# M1502C.net
KiCad netlist of a schematic drawn in EAGLE
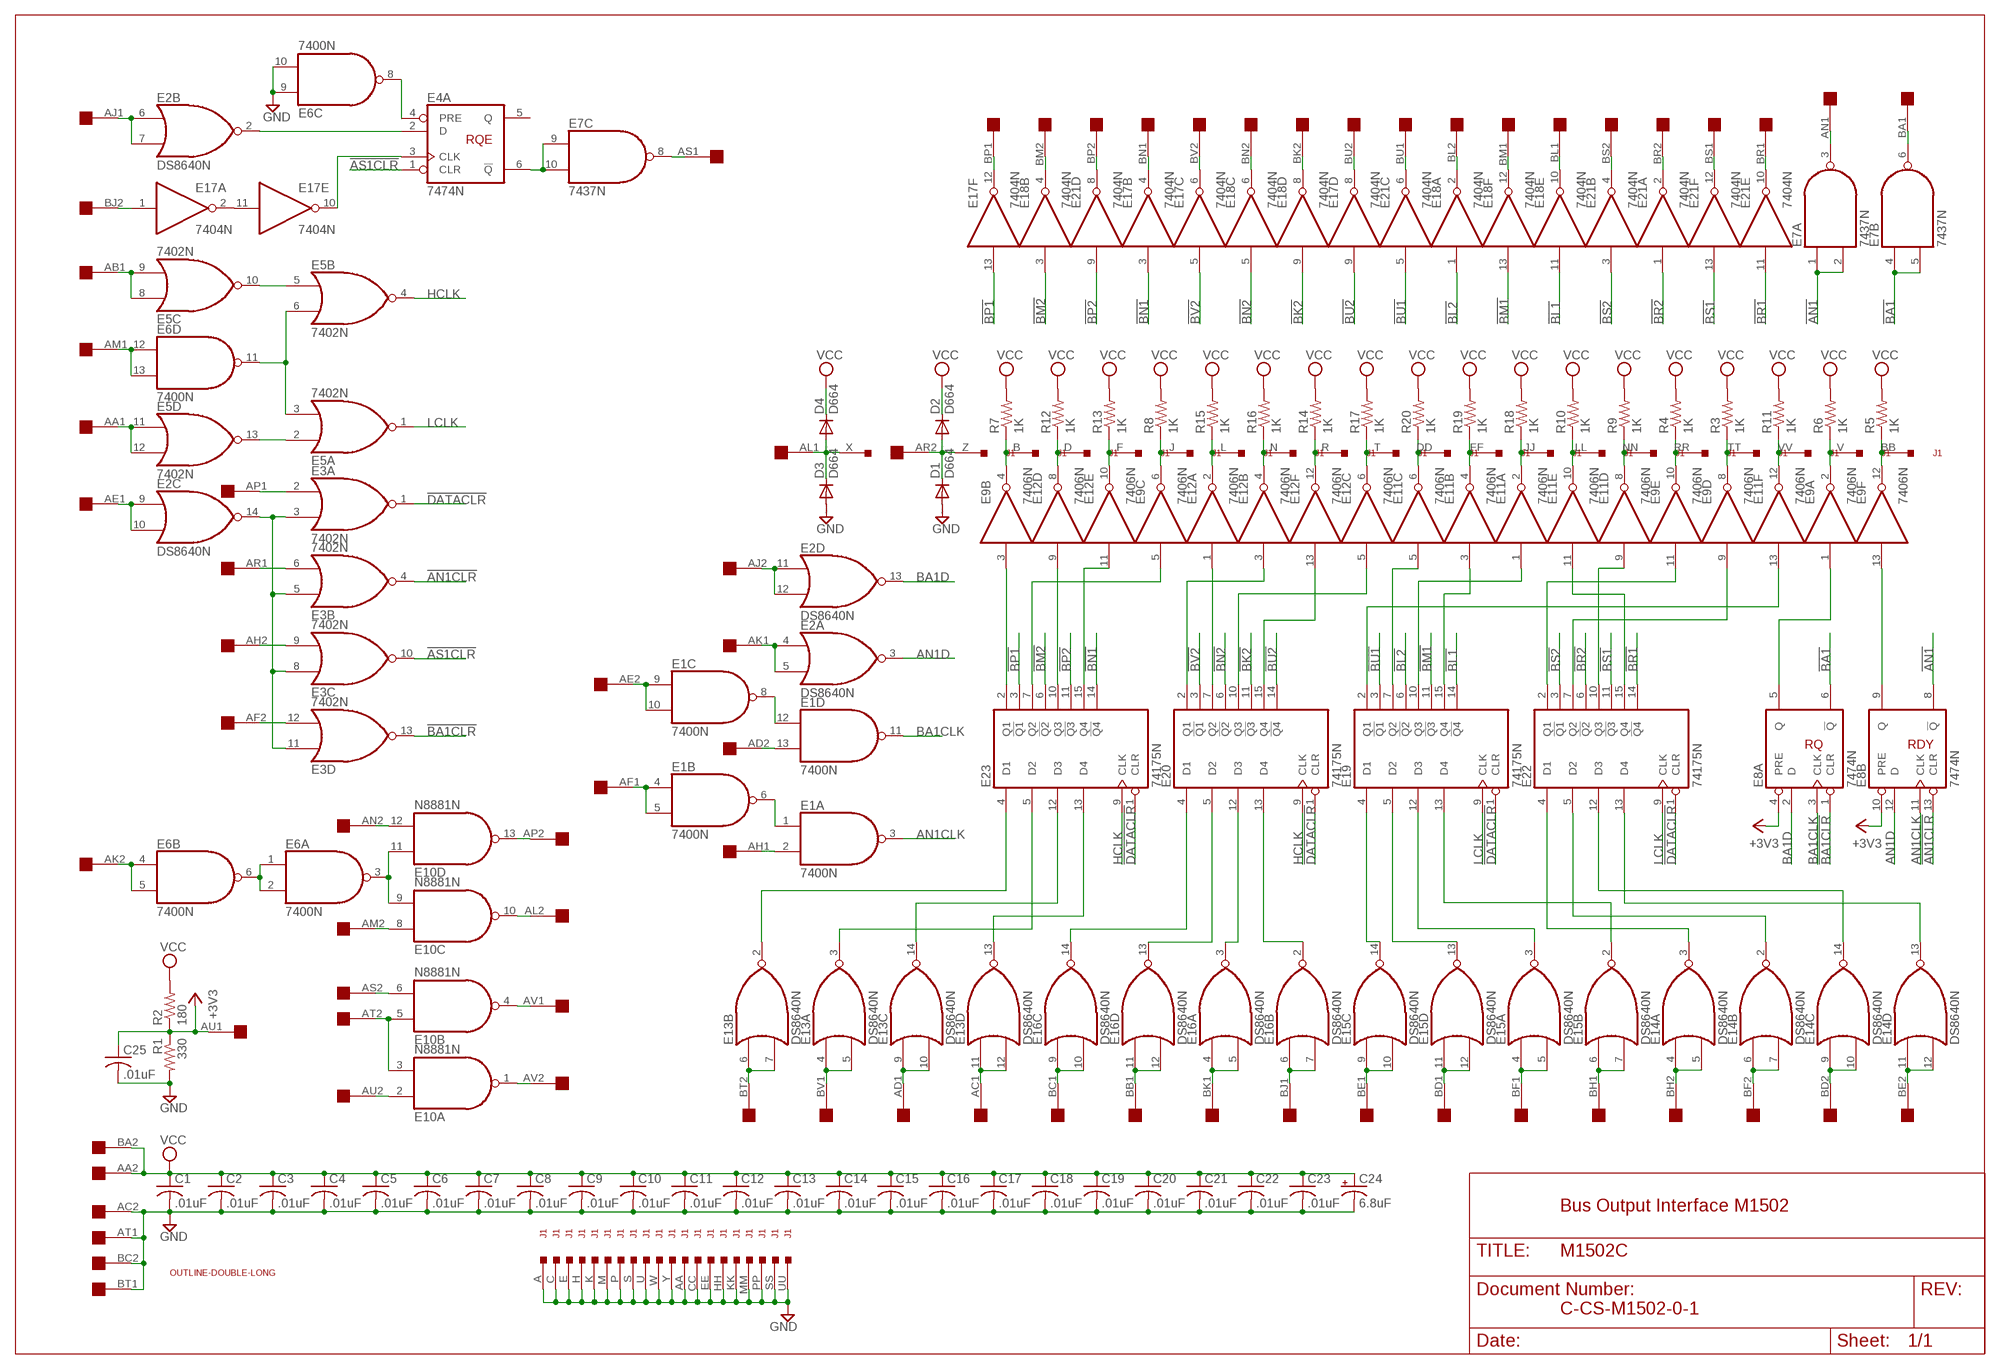
[diagram p0: schematic, sheet 1]

(export (version "E")
  (design (tool "Eeschema 10.0.6"))
  (components
    (comp (ref "C1")
      (value ".01uF")
      (footprint "eagle-import:C075-032X103")
      (libsource (lib "eagle-import") (part "C-US075-032X103"))
    )
    (comp (ref "C2")
      (value ".01uF")
      (footprint "eagle-import:C075-032X103")
      (libsource (lib "eagle-import") (part "C-US075-032X103"))
    )
    (comp (ref "C3")
      (value ".01uF")
      (footprint "eagle-import:C075-032X103")
      (libsource (lib "eagle-import") (part "C-US075-032X103"))
    )
    (comp (ref "C4")
      (value ".01uF")
      (footprint "eagle-import:C075-032X103")
      (libsource (lib "eagle-import") (part "C-US075-032X103"))
    )
    (comp (ref "C5")
      (value ".01uF")
      (footprint "eagle-import:C075-032X103")
      (libsource (lib "eagle-import") (part "C-US075-032X103"))
    )
    (comp (ref "C6")
      (value ".01uF")
      (footprint "eagle-import:C075-032X103")
      (libsource (lib "eagle-import") (part "C-US075-032X103"))
    )
    (comp (ref "C7")
      (value ".01uF")
      (footprint "eagle-import:C075-032X103")
      (libsource (lib "eagle-import") (part "C-US075-032X103"))
    )
    (comp (ref "C8")
      (value ".01uF")
      (footprint "eagle-import:C075-032X103")
      (libsource (lib "eagle-import") (part "C-US075-032X103"))
    )
    (comp (ref "C9")
      (value ".01uF")
      (footprint "eagle-import:C075-032X103")
      (libsource (lib "eagle-import") (part "C-US075-032X103"))
    )
    (comp (ref "C10")
      (value ".01uF")
      (footprint "eagle-import:C075-032X103")
      (libsource (lib "eagle-import") (part "C-US075-032X103"))
    )
    (comp (ref "C11")
      (value ".01uF")
      (footprint "eagle-import:C075-032X103")
      (libsource (lib "eagle-import") (part "C-US075-032X103"))
    )
    (comp (ref "C12")
      (value ".01uF")
      (footprint "eagle-import:C075-032X103")
      (libsource (lib "eagle-import") (part "C-US075-032X103"))
    )
    (comp (ref "C13")
      (value ".01uF")
      (footprint "eagle-import:C075-032X103")
      (libsource (lib "eagle-import") (part "C-US075-032X103"))
    )
    (comp (ref "C14")
      (value ".01uF")
      (footprint "eagle-import:C075-032X103")
      (libsource (lib "eagle-import") (part "C-US075-032X103"))
    )
    (comp (ref "C15")
      (value ".01uF")
      (footprint "eagle-import:C075-032X103")
      (libsource (lib "eagle-import") (part "C-US075-032X103"))
    )
    (comp (ref "C16")
      (value ".01uF")
      (footprint "eagle-import:C075-032X103")
      (libsource (lib "eagle-import") (part "C-US075-032X103"))
    )
    (comp (ref "C17")
      (value ".01uF")
      (footprint "eagle-import:C075-032X103")
      (libsource (lib "eagle-import") (part "C-US075-032X103"))
    )
    (comp (ref "C18")
      (value ".01uF")
      (footprint "eagle-import:C075-032X103")
      (libsource (lib "eagle-import") (part "C-US075-032X103"))
    )
    (comp (ref "C19")
      (value ".01uF")
      (footprint "eagle-import:C075-032X103")
      (libsource (lib "eagle-import") (part "C-US075-032X103"))
    )
    (comp (ref "C20")
      (value ".01uF")
      (footprint "eagle-import:C075-032X103")
      (libsource (lib "eagle-import") (part "C-US075-032X103"))
    )
    (comp (ref "C21")
      (value ".01uF")
      (footprint "eagle-import:C075-032X103")
      (libsource (lib "eagle-import") (part "C-US075-032X103"))
    )
    (comp (ref "C22")
      (value ".01uF")
      (footprint "eagle-import:C075-032X103")
      (libsource (lib "eagle-import") (part "C-US075-032X103"))
    )
    (comp (ref "C23")
      (value ".01uF")
      (footprint "eagle-import:C075-032X103")
      (libsource (lib "eagle-import") (part "C-US075-032X103"))
    )
    (comp (ref "C24")
      (value "6.8uF")
      (footprint "eagle-import:E12-8")
      (libsource (lib "eagle-import") (part "CPOL-USE20-8AXIAL"))
    )
    (comp (ref "C25")
      (value ".01uF")
      (footprint "eagle-import:C075-032X103")
      (libsource (lib "eagle-import") (part "C-US075-032X103"))
    )
    (comp (ref "D1")
      (value "D664")
      (footprint "eagle-import:DO35-10")
      (libsource (lib "eagle-import") (part "DIODE-DO35-10"))
    )
    (comp (ref "D2")
      (value "D664")
      (footprint "eagle-import:DO35-10")
      (libsource (lib "eagle-import") (part "DIODE-DO35-10"))
    )
    (comp (ref "D3")
      (value "D664")
      (footprint "eagle-import:DO35-10")
      (libsource (lib "eagle-import") (part "DIODE-DO35-10"))
    )
    (comp (ref "D4")
      (value "D664")
      (footprint "eagle-import:DO35-10")
      (libsource (lib "eagle-import") (part "DIODE-DO35-10"))
    )
    (comp (ref "E1")
      (value "7400N")
      (footprint "eagle-import:DIL14")
      (libsource (lib "eagle-import") (part "7400N"))
    )
    (comp (ref "E2")
      (value "DS8640N")
      (footprint "eagle-import:DIL14")
      (libsource (lib "eagle-import") (part "DS8640N"))
    )
    (comp (ref "E3")
      (value "7402N")
      (footprint "eagle-import:DIL14")
      (libsource (lib "eagle-import") (part "7402N"))
    )
    (comp (ref "E4")
      (value "7474N")
      (footprint "eagle-import:DIL14")
      (libsource (lib "eagle-import") (part "7474NS"))
    )
    (comp (ref "E5")
      (value "7402N")
      (footprint "eagle-import:DIL14")
      (libsource (lib "eagle-import") (part "7402N"))
    )
    (comp (ref "E6")
      (value "7400N")
      (footprint "eagle-import:DIL14")
      (libsource (lib "eagle-import") (part "7400N"))
    )
    (comp (ref "E7")
      (value "7437N")
      (footprint "eagle-import:DIL14")
      (libsource (lib "eagle-import") (part "7437N"))
    )
    (comp (ref "E8")
      (value "7474N")
      (footprint "eagle-import:DIL14")
      (libsource (lib "eagle-import") (part "7474NS"))
    )
    (comp (ref "E9")
      (value "7406N")
      (footprint "eagle-import:DIL14")
      (libsource (lib "eagle-import") (part "7406N"))
    )
    (comp (ref "E10")
      (value "N8881N")
      (footprint "eagle-import:DIL14")
      (libsource (lib "eagle-import") (part "N8881N"))
    )
    (comp (ref "E11")
      (value "7406N")
      (footprint "eagle-import:DIL14")
      (libsource (lib "eagle-import") (part "7406N"))
    )
    (comp (ref "E12")
      (value "7406N")
      (footprint "eagle-import:DIL14")
      (libsource (lib "eagle-import") (part "7406N"))
    )
    (comp (ref "E13")
      (value "DS8640N")
      (footprint "eagle-import:DIL14")
      (libsource (lib "eagle-import") (part "DS8640N"))
    )
    (comp (ref "E14")
      (value "DS8640N")
      (footprint "eagle-import:DIL14")
      (libsource (lib "eagle-import") (part "DS8640N"))
    )
    (comp (ref "E15")
      (value "DS8640N")
      (footprint "eagle-import:DIL14")
      (libsource (lib "eagle-import") (part "DS8640N"))
    )
    (comp (ref "E16")
      (value "DS8640N")
      (footprint "eagle-import:DIL14")
      (libsource (lib "eagle-import") (part "DS8640N"))
    )
    (comp (ref "E17")
      (value "7404N")
      (footprint "eagle-import:DIL14")
      (libsource (lib "eagle-import") (part "7404N"))
    )
    (comp (ref "E18")
      (value "7404N")
      (footprint "eagle-import:DIL14")
      (libsource (lib "eagle-import") (part "7404N"))
    )
    (comp (ref "E19")
      (value "74175N")
      (footprint "eagle-import:DIL16")
      (libsource (lib "eagle-import") (part "74175N"))
    )
    (comp (ref "E20")
      (value "74175N")
      (footprint "eagle-import:DIL16")
      (libsource (lib "eagle-import") (part "74175N"))
    )
    (comp (ref "E21")
      (value "7404N")
      (footprint "eagle-import:DIL14")
      (libsource (lib "eagle-import") (part "7404N"))
    )
    (comp (ref "E22")
      (value "74175N")
      (footprint "eagle-import:DIL16")
      (libsource (lib "eagle-import") (part "74175N"))
    )
    (comp (ref "E23")
      (value "74175N")
      (footprint "eagle-import:DIL16")
      (libsource (lib "eagle-import") (part "74175N"))
    )
    (comp (ref "J1")
      (value "DEC40PINSH")
      (footprint "eagle-import:DEC40PINH")
      (libsource (lib "eagle-import") (part "DEC40PINSH"))
    )
    (comp (ref "R1")
      (value "330")
      (footprint "eagle-import:0207_10")
      (libsource (lib "eagle-import") (part "R-US_0207/10"))
    )
    (comp (ref "R2")
      (value "180")
      (footprint "eagle-import:0207_10")
      (libsource (lib "eagle-import") (part "R-US_0207/10"))
    )
    (comp (ref "R3")
      (value "1K")
      (footprint "eagle-import:0207_10")
      (libsource (lib "eagle-import") (part "R-US_0207/10"))
    )
    (comp (ref "R4")
      (value "1K")
      (footprint "eagle-import:0207_10")
      (libsource (lib "eagle-import") (part "R-US_0207/10"))
    )
    (comp (ref "R5")
      (value "1K")
      (footprint "eagle-import:0207_10")
      (libsource (lib "eagle-import") (part "R-US_0207/10"))
    )
    (comp (ref "R6")
      (value "1K")
      (footprint "eagle-import:0207_10")
      (libsource (lib "eagle-import") (part "R-US_0207/10"))
    )
    (comp (ref "R7")
      (value "1K")
      (footprint "eagle-import:0207_10")
      (libsource (lib "eagle-import") (part "R-US_0207/10"))
    )
    (comp (ref "R8")
      (value "1K")
      (footprint "eagle-import:0207_10")
      (libsource (lib "eagle-import") (part "R-US_0207/10"))
    )
    (comp (ref "R9")
      (value "1K")
      (footprint "eagle-import:0207_10")
      (libsource (lib "eagle-import") (part "R-US_0207/10"))
    )
    (comp (ref "R10")
      (value "1K")
      (footprint "eagle-import:0207_10")
      (libsource (lib "eagle-import") (part "R-US_0207/10"))
    )
    (comp (ref "R11")
      (value "1K")
      (footprint "eagle-import:0207_10")
      (libsource (lib "eagle-import") (part "R-US_0207/10"))
    )
    (comp (ref "R12")
      (value "1K")
      (footprint "eagle-import:0207_10")
      (libsource (lib "eagle-import") (part "R-US_0207/10"))
    )
    (comp (ref "R13")
      (value "1K")
      (footprint "eagle-import:0207_10")
      (libsource (lib "eagle-import") (part "R-US_0207/10"))
    )
    (comp (ref "R14")
      (value "1K")
      (footprint "eagle-import:0207_10")
      (libsource (lib "eagle-import") (part "R-US_0207/10"))
    )
    (comp (ref "R15")
      (value "1K")
      (footprint "eagle-import:0207_10")
      (libsource (lib "eagle-import") (part "R-US_0207/10"))
    )
    (comp (ref "R16")
      (value "1K")
      (footprint "eagle-import:0207_10")
      (libsource (lib "eagle-import") (part "R-US_0207/10"))
    )
    (comp (ref "R17")
      (value "1K")
      (footprint "eagle-import:0207_10")
      (libsource (lib "eagle-import") (part "R-US_0207/10"))
    )
    (comp (ref "R18")
      (value "1K")
      (footprint "eagle-import:0207_10")
      (libsource (lib "eagle-import") (part "R-US_0207/10"))
    )
    (comp (ref "R19")
      (value "1K")
      (footprint "eagle-import:0207_10")
      (libsource (lib "eagle-import") (part "R-US_0207/10"))
    )
    (comp (ref "R20")
      (value "1K")
      (footprint "eagle-import:0207_10")
      (libsource (lib "eagle-import") (part "R-US_0207/10"))
    )
    (comp (ref "U$1")
      (value "OUTLINE-DOUBLE-LONG")
      (footprint "eagle-import:DOUBLE-LONG")
      (libsource (lib "eagle-import") (part "OUTLINE-DOUBLE-LONG"))
    )
    (comp (ref "U$3")
      (value "DOUBLE")
      (footprint "eagle-import:EDGE-CON4")
      (libsource (lib "eagle-import") (part "DOUBLE"))
    )
  )
  (nets
    (net (code "1") (name "+3V3") (class "Default")
      (node (ref "C25") (pin "1") (pinfunction "1_1") (pintype "passive"))
      (node (ref "E8") (pin "10") (pinfunction "PRE_10") (pintype "input"))
      (node (ref "E8") (pin "4") (pinfunction "PRE_4") (pintype "input"))
      (node (ref "R1") (pin "1") (pinfunction "1_1") (pintype "passive"))
      (node (ref "R2") (pin "1") (pinfunction "1_1") (pintype "passive"))
      (node (ref "U$3") (pin "AU1") (pinfunction "1_AU1") (pintype "bidirectional"))
    )
    (net (code "2") (name "/AN1CLK") (class "Default")
      (node (ref "E1") (pin "3") (pinfunction "O_3") (pintype "output"))
      (node (ref "E8") (pin "11") (pinfunction "CLK_11") (pintype "input"))
    )
    (net (code "3") (name "/AN1D") (class "Default")
      (node (ref "E2") (pin "3") (pinfunction "O_3") (pintype "output"))
      (node (ref "E8") (pin "12") (pinfunction "D_12") (pintype "input"))
    )
    (net (code "4") (name "/BA1CLK") (class "Default")
      (node (ref "E1") (pin "11") (pinfunction "O_11") (pintype "output"))
      (node (ref "E8") (pin "3") (pinfunction "CLK_3") (pintype "input"))
    )
    (net (code "5") (name "/BA1D") (class "Default")
      (node (ref "E2") (pin "13") (pinfunction "O_13") (pintype "output"))
      (node (ref "E8") (pin "2") (pinfunction "D_2") (pintype "input"))
    )
    (net (code "6") (name "/HCLK") (class "Default")
      (node (ref "E20") (pin "9") (pinfunction "CLK_9") (pintype "input"))
      (node (ref "E23") (pin "9") (pinfunction "CLK_9") (pintype "input"))
      (node (ref "E5") (pin "4") (pinfunction "O_4") (pintype "output"))
    )
    (net (code "7") (name "/LCLK") (class "Default")
      (node (ref "E19") (pin "9") (pinfunction "CLK_9") (pintype "input"))
      (node (ref "E22") (pin "9") (pinfunction "CLK_9") (pintype "input"))
      (node (ref "E5") (pin "1") (pinfunction "O_1") (pintype "output"))
    )
    (net (code "8") (name "/~{AN1CLR}") (class "Default")
      (node (ref "E3") (pin "4") (pinfunction "O_4") (pintype "output"))
      (node (ref "E8") (pin "13") (pinfunction "CLR_13") (pintype "input"))
    )
    (net (code "9") (name "/~{AN1}") (class "Default")
      (node (ref "E7") (pin "1") (pinfunction "I0_1") (pintype "input"))
      (node (ref "E7") (pin "2") (pinfunction "I1_2") (pintype "input"))
      (node (ref "E8") (pin "8") (pinfunction "~{Q}_8") (pintype "output"))
    )
    (net (code "10") (name "/~{AS1CLR}") (class "Default")
      (node (ref "E3") (pin "10") (pinfunction "O_10") (pintype "output"))
      (node (ref "E4") (pin "1") (pinfunction "CLR_1") (pintype "input"))
    )
    (net (code "11") (name "/~{BA1CLR}") (class "Default")
      (node (ref "E3") (pin "13") (pinfunction "O_13") (pintype "output"))
      (node (ref "E8") (pin "1") (pinfunction "CLR_1") (pintype "input"))
    )
    (net (code "12") (name "/~{BA1}") (class "Default")
      (node (ref "E7") (pin "4") (pinfunction "I0_4") (pintype "input"))
      (node (ref "E7") (pin "5") (pinfunction "I1_5") (pintype "input"))
      (node (ref "E8") (pin "6") (pinfunction "~{Q}_6") (pintype "output"))
    )
    (net (code "13") (name "/~{BK2}") (class "Default")
      (node (ref "E18") (pin "9") (pinfunction "I_9") (pintype "input"))
      (node (ref "E20") (pin "11") (pinfunction "~{Q3}_11") (pintype "output"))
    )
    (net (code "14") (name "/~{BL1}") (class "Default")
      (node (ref "E18") (pin "11") (pinfunction "I_11") (pintype "input"))
      (node (ref "E19") (pin "14") (pinfunction "~{Q4}_14") (pintype "output"))
    )
    (net (code "15") (name "/~{BL2}") (class "Default")
      (node (ref "E18") (pin "1") (pinfunction "I_1") (pintype "input"))
      (node (ref "E19") (pin "6") (pinfunction "~{Q2}_6") (pintype "output"))
    )
    (net (code "16") (name "/~{BM1}") (class "Default")
      (node (ref "E18") (pin "13") (pinfunction "I_13") (pintype "input"))
      (node (ref "E19") (pin "11") (pinfunction "~{Q3}_11") (pintype "output"))
    )
    (net (code "17") (name "/~{BM2}") (class "Default")
      (node (ref "E18") (pin "3") (pinfunction "I_3") (pintype "input"))
      (node (ref "E23") (pin "6") (pinfunction "~{Q2}_6") (pintype "output"))
    )
    (net (code "18") (name "/~{BN1}") (class "Default")
      (node (ref "E17") (pin "3") (pinfunction "I_3") (pintype "input"))
      (node (ref "E23") (pin "14") (pinfunction "~{Q4}_14") (pintype "output"))
    )
    (net (code "19") (name "/~{BN2}") (class "Default")
      (node (ref "E18") (pin "5") (pinfunction "I_5") (pintype "input"))
      (node (ref "E20") (pin "6") (pinfunction "~{Q2}_6") (pintype "output"))
    )
    (net (code "20") (name "/~{BP1}") (class "Default")
      (node (ref "E17") (pin "13") (pinfunction "I_13") (pintype "input"))
      (node (ref "E23") (pin "3") (pinfunction "~{Q1}_3") (pintype "output"))
    )
    (net (code "21") (name "/~{BP2}") (class "Default")
      (node (ref "E21") (pin "9") (pinfunction "I_9") (pintype "input"))
      (node (ref "E23") (pin "11") (pinfunction "~{Q3}_11") (pintype "output"))
    )
    (net (code "22") (name "/~{BR1}") (class "Default")
      (node (ref "E21") (pin "11") (pinfunction "I_11") (pintype "input"))
      (node (ref "E22") (pin "14") (pinfunction "~{Q4}_14") (pintype "output"))
    )
    (net (code "23") (name "/~{BR2}") (class "Default")
      (node (ref "E21") (pin "1") (pinfunction "I_1") (pintype "input"))
      (node (ref "E22") (pin "6") (pinfunction "~{Q2}_6") (pintype "output"))
    )
    (net (code "24") (name "/~{BS1}") (class "Default")
      (node (ref "E21") (pin "13") (pinfunction "I_13") (pintype "input"))
      (node (ref "E22") (pin "11") (pinfunction "~{Q3}_11") (pintype "output"))
    )
    (net (code "25") (name "/~{BS2}") (class "Default")
      (node (ref "E21") (pin "3") (pinfunction "I_3") (pintype "input"))
      (node (ref "E22") (pin "3") (pinfunction "~{Q1}_3") (pintype "output"))
    )
    (net (code "26") (name "/~{BU1}") (class "Default")
      (node (ref "E19") (pin "3") (pinfunction "~{Q1}_3") (pintype "output"))
      (node (ref "E21") (pin "5") (pinfunction "I_5") (pintype "input"))
    )
    (net (code "27") (name "/~{BU2}") (class "Default")
      (node (ref "E17") (pin "9") (pinfunction "I_9") (pintype "input"))
      (node (ref "E20") (pin "14") (pinfunction "~{Q4}_14") (pintype "output"))
    )
    (net (code "28") (name "/~{BV2}") (class "Default")
      (node (ref "E17") (pin "5") (pinfunction "I_5") (pintype "input"))
      (node (ref "E20") (pin "3") (pinfunction "~{Q1}_3") (pintype "output"))
    )
    (net (code "29") (name "/~{DATACLR}") (class "Default")
      (node (ref "E19") (pin "1") (pinfunction "CLR_1") (pintype "input"))
      (node (ref "E20") (pin "1") (pinfunction "CLR_1") (pintype "input"))
      (node (ref "E22") (pin "1") (pinfunction "CLR_1") (pintype "input"))
      (node (ref "E23") (pin "1") (pinfunction "CLR_1") (pintype "input"))
      (node (ref "E3") (pin "1") (pinfunction "O_1") (pintype "output"))
    )
    (net (code "30") (name "GND") (class "Default")
      (node (ref "C1") (pin "2") (pinfunction "2_2") (pintype "passive"))
      (node (ref "C10") (pin "2") (pinfunction "2_2") (pintype "passive"))
      (node (ref "C11") (pin "2") (pinfunction "2_2") (pintype "passive"))
      (node (ref "C12") (pin "2") (pinfunction "2_2") (pintype "passive"))
      (node (ref "C13") (pin "2") (pinfunction "2_2") (pintype "passive"))
      (node (ref "C14") (pin "2") (pinfunction "2_2") (pintype "passive"))
      (node (ref "C15") (pin "2") (pinfunction "2_2") (pintype "passive"))
      (node (ref "C16") (pin "2") (pinfunction "2_2") (pintype "passive"))
      (node (ref "C17") (pin "2") (pinfunction "2_2") (pintype "passive"))
      (node (ref "C18") (pin "2") (pinfunction "2_2") (pintype "passive"))
      (node (ref "C19") (pin "2") (pinfunction "2_2") (pintype "passive"))
      (node (ref "C2") (pin "2") (pinfunction "2_2") (pintype "passive"))
      (node (ref "C20") (pin "2") (pinfunction "2_2") (pintype "passive"))
      (node (ref "C21") (pin "2") (pinfunction "2_2") (pintype "passive"))
      (node (ref "C22") (pin "2") (pinfunction "2_2") (pintype "passive"))
      (node (ref "C23") (pin "2") (pinfunction "2_2") (pintype "passive"))
      (node (ref "C24") (pin "-") (pinfunction "-_-") (pintype "passive"))
      (node (ref "C25") (pin "2") (pinfunction "2_2") (pintype "passive"))
      (node (ref "C3") (pin "2") (pinfunction "2_2") (pintype "passive"))
      (node (ref "C4") (pin "2") (pinfunction "2_2") (pintype "passive"))
      (node (ref "C5") (pin "2") (pinfunction "2_2") (pintype "passive"))
      (node (ref "C6") (pin "2") (pinfunction "2_2") (pintype "passive"))
      (node (ref "C7") (pin "2") (pinfunction "2_2") (pintype "passive"))
      (node (ref "C8") (pin "2") (pinfunction "2_2") (pintype "passive"))
      (node (ref "C9") (pin "2") (pinfunction "2_2") (pintype "passive"))
      (node (ref "D1") (pin "A") (pinfunction "A_A") (pintype "passive"))
      (node (ref "D3") (pin "A") (pinfunction "A_A") (pintype "passive"))
      (node (ref "E6") (pin "10") (pinfunction "I1_10") (pintype "input"))
      (node (ref "E6") (pin "9") (pinfunction "I0_9") (pintype "input"))
      (node (ref "J1") (pin "A") (pinfunction "P$2_A") (pintype "passive"))
      (node (ref "J1") (pin "AA") (pinfunction "P$2_AA") (pintype "passive"))
      (node (ref "J1") (pin "C") (pinfunction "P$2_C") (pintype "passive"))
      (node (ref "J1") (pin "CC") (pinfunction "P$2_CC") (pintype "passive"))
      (node (ref "J1") (pin "E") (pinfunction "P$2_E") (pintype "passive"))
      (node (ref "J1") (pin "EE") (pinfunction "P$2_EE") (pintype "passive"))
      (node (ref "J1") (pin "H") (pinfunction "P$2_H") (pintype "passive"))
      (node (ref "J1") (pin "HH") (pinfunction "P$2_HH") (pintype "passive"))
      (node (ref "J1") (pin "K") (pinfunction "P$2_K") (pintype "passive"))
      (node (ref "J1") (pin "KK") (pinfunction "P$2_KK") (pintype "passive"))
      (node (ref "J1") (pin "M") (pinfunction "P$2_M") (pintype "passive"))
      (node (ref "J1") (pin "MM") (pinfunction "P$2_MM") (pintype "passive"))
      (node (ref "J1") (pin "P") (pinfunction "P$2_P") (pintype "passive"))
      (node (ref "J1") (pin "PP") (pinfunction "P$2_PP") (pintype "passive"))
      (node (ref "J1") (pin "S") (pinfunction "P$2_S") (pintype "passive"))
      (node (ref "J1") (pin "SS") (pinfunction "P$2_SS") (pintype "passive"))
      (node (ref "J1") (pin "U") (pinfunction "P$2_U") (pintype "passive"))
      (node (ref "J1") (pin "UU") (pinfunction "P$2_UU") (pintype "passive"))
      (node (ref "J1") (pin "W") (pinfunction "P$2_W") (pintype "passive"))
      (node (ref "J1") (pin "Y") (pinfunction "P$2_Y") (pintype "passive"))
      (node (ref "R1") (pin "2") (pinfunction "2_2") (pintype "passive"))
      (node (ref "U$3") (pin "AC2") (pinfunction "1_AC2") (pintype "bidirectional"))
      (node (ref "U$3") (pin "AT1") (pinfunction "1_AT1") (pintype "bidirectional"))
      (node (ref "U$3") (pin "BC2") (pinfunction "1_BC2") (pintype "bidirectional"))
      (node (ref "U$3") (pin "BT1") (pinfunction "1_BT1") (pintype "bidirectional"))
    )
    (net (code "31") (name "Net-(E1A-I0)") (class "Default")
      (node (ref "E1") (pin "1") (pinfunction "I0_1") (pintype "input"))
      (node (ref "E1") (pin "6") (pinfunction "O_6") (pintype "output"))
    )
    (net (code "32") (name "Net-(E1A-I1)") (class "Default")
      (node (ref "E1") (pin "2") (pinfunction "I1_2") (pintype "input"))
      (node (ref "U$3") (pin "AH1") (pinfunction "1_AH1") (pintype "bidirectional"))
    )
    (net (code "33") (name "Net-(E1B-I0)") (class "Default")
      (node (ref "E1") (pin "4") (pinfunction "I0_4") (pintype "input"))
      (node (ref "E1") (pin "5") (pinfunction "I1_5") (pintype "input"))
      (node (ref "U$3") (pin "AF1") (pinfunction "1_AF1") (pintype "bidirectional"))
    )
    (net (code "34") (name "Net-(E1C-I0)") (class "Default")
      (node (ref "E1") (pin "10") (pinfunction "I1_10") (pintype "input"))
      (node (ref "E1") (pin "9") (pinfunction "I0_9") (pintype "input"))
      (node (ref "U$3") (pin "AE2") (pinfunction "1_AE2") (pintype "bidirectional"))
    )
    (net (code "35") (name "Net-(E1C-O)") (class "Default")
      (node (ref "E1") (pin "12") (pinfunction "I0_12") (pintype "input"))
      (node (ref "E1") (pin "8") (pinfunction "O_8") (pintype "output"))
    )
    (net (code "36") (name "Net-(E1D-I1)") (class "Default")
      (node (ref "E1") (pin "13") (pinfunction "I1_13") (pintype "input"))
      (node (ref "U$3") (pin "AD2") (pinfunction "1_AD2") (pintype "bidirectional"))
    )
    (net (code "37") (name "Net-(E2A-I0)") (class "Default")
      (node (ref "E2") (pin "4") (pinfunction "I0_4") (pintype "input"))
      (node (ref "E2") (pin "5") (pinfunction "I1_5") (pintype "input"))
      (node (ref "U$3") (pin "AK1") (pinfunction "1_AK1") (pintype "bidirectional"))
    )
    (net (code "38") (name "Net-(E2B-I0)") (class "Default")
      (node (ref "E2") (pin "6") (pinfunction "I0_6") (pintype "input"))
      (node (ref "E2") (pin "7") (pinfunction "I1_7") (pintype "input"))
      (node (ref "U$3") (pin "AJ1") (pinfunction "1_AJ1") (pintype "bidirectional"))
    )
    (net (code "39") (name "Net-(E2B-O)") (class "Default")
      (node (ref "E2") (pin "2") (pinfunction "O_2") (pintype "output"))
      (node (ref "E4") (pin "2") (pinfunction "D_2") (pintype "input"))
    )
    (net (code "40") (name "Net-(E2C-I0)") (class "Default")
      (node (ref "E2") (pin "10") (pinfunction "I1_10") (pintype "input"))
      (node (ref "E2") (pin "9") (pinfunction "I0_9") (pintype "input"))
      (node (ref "U$3") (pin "AE1") (pinfunction "1_AE1") (pintype "bidirectional"))
    )
    (net (code "41") (name "Net-(E2C-O)") (class "Default")
      (node (ref "E2") (pin "14") (pinfunction "O_14") (pintype "output"))
      (node (ref "E3") (pin "11") (pinfunction "I0_11") (pintype "input"))
      (node (ref "E3") (pin "3") (pinfunction "I1_3") (pintype "input"))
      (node (ref "E3") (pin "5") (pinfunction "I0_5") (pintype "input"))
      (node (ref "E3") (pin "8") (pinfunction "I0_8") (pintype "input"))
    )
    (net (code "42") (name "Net-(E2D-I0)") (class "Default")
      (node (ref "E2") (pin "11") (pinfunction "I0_11") (pintype "input"))
      (node (ref "E2") (pin "12") (pinfunction "I1_12") (pintype "input"))
      (node (ref "U$3") (pin "AJ2") (pinfunction "1_AJ2") (pintype "bidirectional"))
    )
    (net (code "43") (name "Net-(E3A-I0)") (class "Default")
      (node (ref "E3") (pin "2") (pinfunction "I0_2") (pintype "input"))
      (node (ref "U$3") (pin "AP1") (pinfunction "1_AP1") (pintype "bidirectional"))
    )
    (net (code "44") (name "Net-(E3B-I1)") (class "Default")
      (node (ref "E3") (pin "6") (pinfunction "I1_6") (pintype "input"))
      (node (ref "U$3") (pin "AR1") (pinfunction "1_AR1") (pintype "bidirectional"))
    )
    (net (code "45") (name "Net-(E3C-I1)") (class "Default")
      (node (ref "E3") (pin "9") (pinfunction "I1_9") (pintype "input"))
      (node (ref "U$3") (pin "AH2") (pinfunction "1_AH2") (pintype "bidirectional"))
    )
    (net (code "46") (name "Net-(E3D-I1)") (class "Default")
      (node (ref "E3") (pin "12") (pinfunction "I1_12") (pintype "input"))
      (node (ref "U$3") (pin "AF2") (pinfunction "1_AF2") (pintype "bidirectional"))
    )
    (net (code "47") (name "Net-(E4A-PRE)") (class "Default")
      (node (ref "E4") (pin "4") (pinfunction "PRE_4") (pintype "input"))
      (node (ref "E6") (pin "8") (pinfunction "O_8") (pintype "output"))
    )
    (net (code "48") (name "Net-(E4A-~{Q})") (class "Default")
      (node (ref "E4") (pin "6") (pinfunction "~{Q}_6") (pintype "output"))
      (node (ref "E7") (pin "10") (pinfunction "I1_10") (pintype "input"))
      (node (ref "E7") (pin "9") (pinfunction "I0_9") (pintype "input"))
    )
    (net (code "49") (name "Net-(E5A-I0)") (class "Default")
      (node (ref "E5") (pin "13") (pinfunction "O_13") (pintype "output"))
      (node (ref "E5") (pin "2") (pinfunction "I0_2") (pintype "input"))
    )
    (net (code "50") (name "Net-(E5A-I1)") (class "Default")
      (node (ref "E5") (pin "3") (pinfunction "I1_3") (pintype "input"))
      (node (ref "E5") (pin "6") (pinfunction "I1_6") (pintype "input"))
      (node (ref "E6") (pin "11") (pinfunction "O_11") (pintype "output"))
    )
    (net (code "51") (name "Net-(E5B-I0)") (class "Default")
      (node (ref "E5") (pin "10") (pinfunction "O_10") (pintype "output"))
      (node (ref "E5") (pin "5") (pinfunction "I0_5") (pintype "input"))
    )
    (net (code "52") (name "Net-(E5C-I0)") (class "Default")
      (node (ref "E5") (pin "8") (pinfunction "I0_8") (pintype "input"))
      (node (ref "E5") (pin "9") (pinfunction "I1_9") (pintype "input"))
      (node (ref "U$3") (pin "AB1") (pinfunction "1_AB1") (pintype "bidirectional"))
    )
    (net (code "53") (name "Net-(E5D-I0)") (class "Default")
      (node (ref "E5") (pin "11") (pinfunction "I0_11") (pintype "input"))
      (node (ref "E5") (pin "12") (pinfunction "I1_12") (pintype "input"))
      (node (ref "U$3") (pin "AA1") (pinfunction "1_AA1") (pintype "bidirectional"))
    )
    (net (code "54") (name "Net-(E6A-I0)") (class "Default")
      (node (ref "E6") (pin "1") (pinfunction "I0_1") (pintype "input"))
      (node (ref "E6") (pin "2") (pinfunction "I1_2") (pintype "input"))
      (node (ref "E6") (pin "6") (pinfunction "O_6") (pintype "output"))
    )
    (net (code "55") (name "Net-(E6B-I0)") (class "Default")
      (node (ref "E6") (pin "4") (pinfunction "I0_4") (pintype "input"))
      (node (ref "E6") (pin "5") (pinfunction "I1_5") (pintype "input"))
      (node (ref "U$3") (pin "AK2") (pinfunction "1_AK2") (pintype "bidirectional"))
    )
    (net (code "56") (name "Net-(E6D-I0)") (class "Default")
      (node (ref "E6") (pin "12") (pinfunction "I0_12") (pintype "input"))
      (node (ref "E6") (pin "13") (pinfunction "I1_13") (pintype "input"))
      (node (ref "U$3") (pin "AM1") (pinfunction "1_AM1") (pintype "bidirectional"))
    )
    (net (code "57") (name "Net-(E7A-O)") (class "Default")
      (node (ref "E7") (pin "3") (pinfunction "O_3") (pintype "output"))
      (node (ref "U$3") (pin "AN1") (pinfunction "1_AN1") (pintype "bidirectional"))
    )
    (net (code "58") (name "Net-(E7B-O)") (class "Default")
      (node (ref "E7") (pin "6") (pinfunction "O_6") (pintype "output"))
      (node (ref "U$3") (pin "BA1") (pinfunction "1_BA1") (pintype "bidirectional"))
    )
    (net (code "59") (name "Net-(E7C-O)") (class "Default")
      (node (ref "E7") (pin "8") (pinfunction "O_8") (pintype "output"))
      (node (ref "U$3") (pin "AS1") (pinfunction "1_AS1") (pintype "bidirectional"))
    )
    (net (code "60") (name "Net-(E8A-Q)") (class "Default")
      (node (ref "E8") (pin "5") (pinfunction "Q_5") (pintype "output"))
      (node (ref "E9") (pin "1") (pinfunction "I_1") (pintype "input"))
    )
    (net (code "61") (name "Net-(E8B-Q)") (class "Default")
      (node (ref "E8") (pin "9") (pinfunction "Q_9") (pintype "output"))
      (node (ref "E9") (pin "13") (pinfunction "I_13") (pintype "input"))
    )
    (net (code "62") (name "Net-(E9A-O)") (class "Default")
      (node (ref "E9") (pin "2") (pinfunction "O_2") (pintype "open_collector"))
      (node (ref "J1") (pin "V") (pinfunction "P$2_V") (pintype "passive"))
      (node (ref "R6") (pin "1") (pinfunction "1_1") (pintype "passive"))
    )
    (net (code "63") (name "Net-(E9B-O)") (class "Default")
      (node (ref "E9") (pin "4") (pinfunction "O_4") (pintype "open_collector"))
      (node (ref "J1") (pin "B") (pinfunction "P$2_B") (pintype "passive"))
      (node (ref "R7") (pin "1") (pinfunction "1_1") (pintype "passive"))
    )
    (net (code "64") (name "Net-(E9C-O)") (class "Default")
      (node (ref "E9") (pin "6") (pinfunction "O_6") (pintype "open_collector"))
      (node (ref "J1") (pin "J") (pinfunction "P$2_J") (pintype "passive"))
      (node (ref "R8") (pin "1") (pinfunction "1_1") (pintype "passive"))
    )
    (net (code "65") (name "Net-(E9D-O)") (class "Default")
      (node (ref "E9") (pin "8") (pinfunction "O_8") (pintype "open_collector"))
      (node (ref "J1") (pin "TT") (pinfunction "P$2_TT") (pintype "passive"))
      (node (ref "R3") (pin "1") (pinfunction "1_1") (pintype "passive"))
    )
    (net (code "66") (name "Net-(E9E-O)") (class "Default")
      (node (ref "E9") (pin "10") (pinfunction "O_10") (pintype "open_collector"))
      (node (ref "J1") (pin "RR") (pinfunction "P$2_RR") (pintype "passive"))
      (node (ref "R4") (pin "1") (pinfunction "1_1") (pintype "passive"))
    )
    (net (code "67") (name "Net-(E9F-O)") (class "Default")
      (node (ref "E9") (pin "12") (pinfunction "O_12") (pintype "open_collector"))
      (node (ref "J1") (pin "BB") (pinfunction "P$2_BB") (pintype "passive"))
      (node (ref "R5") (pin "1") (pinfunction "1_1") (pintype "passive"))
    )
    (net (code "68") (name "Net-(E10A-I0)") (class "Default")
      (node (ref "E10") (pin "2") (pinfunction "I0_2") (pintype "input"))
      (node (ref "U$3") (pin "AU2") (pinfunction "1_AU2") (pintype "bidirectional"))
    )
    (net (code "69") (name "Net-(E10A-I1)") (class "Default")
      (node (ref "E10") (pin "3") (pinfunction "I1_3") (pintype "input"))
      (node (ref "E10") (pin "5") (pinfunction "I0_5") (pintype "input"))
      (node (ref "U$3") (pin "AT2") (pinfunction "1_AT2") (pintype "bidirectional"))
    )
    (net (code "70") (name "Net-(E10A-O)") (class "Default")
      (node (ref "E10") (pin "1") (pinfunction "O_1") (pintype "open_collector"))
      (node (ref "U$3") (pin "AV2") (pinfunction "1_AV2") (pintype "bidirectional"))
    )
    (net (code "71") (name "Net-(E10B-I1)") (class "Default")
      (node (ref "E10") (pin "6") (pinfunction "I1_6") (pintype "input"))
      (node (ref "U$3") (pin "AS2") (pinfunction "1_AS2") (pintype "bidirectional"))
    )
    (net (code "72") (name "Net-(E10B-O)") (class "Default")
      (node (ref "E10") (pin "4") (pinfunction "O_4") (pintype "open_collector"))
      (node (ref "U$3") (pin "AV1") (pinfunction "1_AV1") (pintype "bidirectional"))
    )
    (net (code "73") (name "Net-(E10C-I0)") (class "Default")
      (node (ref "E10") (pin "8") (pinfunction "I0_8") (pintype "input"))
      (node (ref "U$3") (pin "AM2") (pinfunction "1_AM2") (pintype "bidirectional"))
    )
    (net (code "74") (name "Net-(E10C-I1)") (class "Default")
      (node (ref "E10") (pin "11") (pinfunction "I0_11") (pintype "input"))
      (node (ref "E10") (pin "9") (pinfunction "I1_9") (pintype "input"))
      (node (ref "E6") (pin "3") (pinfunction "O_3") (pintype "output"))
    )
    (net (code "75") (name "Net-(E10C-O)") (class "Default")
      (node (ref "E10") (pin "10") (pinfunction "O_10") (pintype "open_collector"))
      (node (ref "U$3") (pin "AL2") (pinfunction "1_AL2") (pintype "bidirectional"))
    )
    (net (code "76") (name "Net-(E10D-I1)") (class "Default")
      (node (ref "E10") (pin "12") (pinfunction "I1_12") (pintype "input"))
      (node (ref "U$3") (pin "AN2") (pinfunction "1_AN2") (pintype "bidirectional"))
    )
    (net (code "77") (name "Net-(E10D-O)") (class "Default")
      (node (ref "E10") (pin "13") (pinfunction "O_13") (pintype "open_collector"))
      (node (ref "U$3") (pin "AP2") (pinfunction "1_AP2") (pintype "bidirectional"))
    )
    (net (code "78") (name "Net-(E11A-I)") (class "Default")
      (node (ref "E11") (pin "1") (pinfunction "I_1") (pintype "input"))
      (node (ref "E19") (pin "10") (pinfunction "Q3_10") (pintype "output"))
    )
    (net (code "79") (name "Net-(E11A-O)") (class "Default")
      (node (ref "E11") (pin "2") (pinfunction "O_2") (pintype "open_collector"))
      (node (ref "J1") (pin "JJ") (pinfunction "P$2_JJ") (pintype "passive"))
      (node (ref "R18") (pin "1") (pinfunction "1_1") (pintype "passive"))
    )
    (net (code "80") (name "Net-(E11B-I)") (class "Default")
      (node (ref "E11") (pin "3") (pinfunction "I_3") (pintype "input"))
      (node (ref "E19") (pin "15") (pinfunction "Q4_15") (pintype "output"))
    )
    (net (code "81") (name "Net-(E11B-O)") (class "Default")
      (node (ref "E11") (pin "4") (pinfunction "O_4") (pintype "open_collector"))
      (node (ref "J1") (pin "FF") (pinfunction "P$2_FF") (pintype "passive"))
      (node (ref "R19") (pin "1") (pinfunction "1_1") (pintype "passive"))
    )
    (net (code "82") (name "Net-(E11C-I)") (class "Default")
      (node (ref "E11") (pin "5") (pinfunction "I_5") (pintype "input"))
      (node (ref "E19") (pin "7") (pinfunction "Q2_7") (pintype "output"))
    )
    (net (code "83") (name "Net-(E11C-O)") (class "Default")
      (node (ref "E11") (pin "6") (pinfunction "O_6") (pintype "open_collector"))
      (node (ref "J1") (pin "DD") (pinfunction "P$2_DD") (pintype "passive"))
      (node (ref "R20") (pin "1") (pinfunction "1_1") (pintype "passive"))
    )
    (net (code "84") (name "Net-(E11D-I)") (class "Default")
      (node (ref "E11") (pin "9") (pinfunction "I_9") (pintype "input"))
      (node (ref "E22") (pin "10") (pinfunction "Q3_10") (pintype "output"))
    )
    (net (code "85") (name "Net-(E11D-O)") (class "Default")
      (node (ref "E11") (pin "8") (pinfunction "O_8") (pintype "open_collector"))
      (node (ref "J1") (pin "NN") (pinfunction "P$2_NN") (pintype "passive"))
      (node (ref "R9") (pin "1") (pinfunction "1_1") (pintype "passive"))
    )
    (net (code "86") (name "Net-(E11E-I)") (class "Default")
      (node (ref "E11") (pin "11") (pinfunction "I_11") (pintype "input"))
      (node (ref "E22") (pin "15") (pinfunction "Q4_15") (pintype "output"))
    )
    (net (code "87") (name "Net-(E11E-O)") (class "Default")
      (node (ref "E11") (pin "10") (pinfunction "O_10") (pintype "open_collector"))
      (node (ref "J1") (pin "LL") (pinfunction "P$2_LL") (pintype "passive"))
      (node (ref "R10") (pin "1") (pinfunction "1_1") (pintype "passive"))
    )
    (net (code "88") (name "Net-(E11F-I)") (class "Default")
      (node (ref "E11") (pin "13") (pinfunction "I_13") (pintype "input"))
      (node (ref "E19") (pin "2") (pinfunction "Q1_2") (pintype "output"))
    )
    (net (code "89") (name "Net-(E11F-O)") (class "Default")
      (node (ref "E11") (pin "12") (pinfunction "O_12") (pintype "open_collector"))
      (node (ref "J1") (pin "VV") (pinfunction "P$2_VV") (pintype "passive"))
      (node (ref "R11") (pin "1") (pinfunction "1_1") (pintype "passive"))
    )
    (net (code "90") (name "Net-(E12A-I)") (class "Default")
      (node (ref "E12") (pin "1") (pinfunction "I_1") (pintype "input"))
      (node (ref "E20") (pin "7") (pinfunction "Q2_7") (pintype "output"))
    )
    (net (code "91") (name "Net-(E12A-O)") (class "Default")
      (node (ref "E12") (pin "2") (pinfunction "O_2") (pintype "open_collector"))
      (node (ref "J1") (pin "L") (pinfunction "P$2_L") (pintype "passive"))
      (node (ref "R15") (pin "1") (pinfunction "1_1") (pintype "passive"))
    )
    (net (code "92") (name "Net-(E12B-I)") (class "Default")
      (node (ref "E12") (pin "3") (pinfunction "I_3") (pintype "input"))
      (node (ref "E20") (pin "2") (pinfunction "Q1_2") (pintype "output"))
    )
    (net (code "93") (name "Net-(E12B-O)") (class "Default")
      (node (ref "E12") (pin "4") (pinfunction "O_4") (pintype "open_collector"))
      (node (ref "J1") (pin "N") (pinfunction "P$2_N") (pintype "passive"))
      (node (ref "R16") (pin "1") (pinfunction "1_1") (pintype "passive"))
    )
    (net (code "94") (name "Net-(E12C-I)") (class "Default")
      (node (ref "E12") (pin "5") (pinfunction "I_5") (pintype "input"))
      (node (ref "E20") (pin "10") (pinfunction "Q3_10") (pintype "output"))
    )
    (net (code "95") (name "Net-(E12C-O)") (class "Default")
      (node (ref "E12") (pin "6") (pinfunction "O_6") (pintype "open_collector"))
      (node (ref "J1") (pin "T") (pinfunction "P$2_T") (pintype "passive"))
      (node (ref "R17") (pin "1") (pinfunction "1_1") (pintype "passive"))
    )
    (net (code "96") (name "Net-(E12D-I)") (class "Default")
      (node (ref "E12") (pin "9") (pinfunction "I_9") (pintype "input"))
      (node (ref "E23") (pin "10") (pinfunction "Q3_10") (pintype "output"))
    )
    (net (code "97") (name "Net-(E12D-O)") (class "Default")
      (node (ref "E12") (pin "8") (pinfunction "O_8") (pintype "open_collector"))
      (node (ref "J1") (pin "D") (pinfunction "P$2_D") (pintype "passive"))
      (node (ref "R12") (pin "1") (pinfunction "1_1") (pintype "passive"))
    )
    (net (code "98") (name "Net-(E12E-I)") (class "Default")
      (node (ref "E12") (pin "11") (pinfunction "I_11") (pintype "input"))
      (node (ref "E23") (pin "15") (pinfunction "Q4_15") (pintype "output"))
    )
    (net (code "99") (name "Net-(E12E-O)") (class "Default")
      (node (ref "E12") (pin "10") (pinfunction "O_10") (pintype "open_collector"))
      (node (ref "J1") (pin "F") (pinfunction "P$2_F") (pintype "passive"))
      (node (ref "R13") (pin "1") (pinfunction "1_1") (pintype "passive"))
    )
    (net (code "100") (name "Net-(E12F-I)") (class "Default")
      (node (ref "E12") (pin "13") (pinfunction "I_13") (pintype "input"))
      (node (ref "E20") (pin "15") (pinfunction "Q4_15") (pintype "output"))
    )
    (net (code "101") (name "Net-(E12F-O)") (class "Default")
      (node (ref "E12") (pin "12") (pinfunction "O_12") (pintype "open_collector"))
      (node (ref "J1") (pin "R") (pinfunction "P$2_R") (pintype "passive"))
      (node (ref "R14") (pin "1") (pinfunction "1_1") (pintype "passive"))
    )
    (net (code "102") (name "Net-(E13A-I0)") (class "Default")
      (node (ref "E13") (pin "4") (pinfunction "I0_4") (pintype "input"))
      (node (ref "E13") (pin "5") (pinfunction "I1_5") (pintype "input"))
      (node (ref "U$3") (pin "BV1") (pinfunction "1_BV1") (pintype "bidirectional"))
    )
    (net (code "103") (name "Net-(E13A-O)") (class "Default")
      (node (ref "E13") (pin "3") (pinfunction "O_3") (pintype "output"))
      (node (ref "E23") (pin "5") (pinfunction "D2_5") (pintype "input"))
    )
    (net (code "104") (name "Net-(E13B-I0)") (class "Default")
      (node (ref "E13") (pin "6") (pinfunction "I0_6") (pintype "input"))
      (node (ref "E13") (pin "7") (pinfunction "I1_7") (pintype "input"))
      (node (ref "U$3") (pin "BT2") (pinfunction "1_BT2") (pintype "bidirectional"))
    )
    (net (code "105") (name "Net-(E13B-O)") (class "Default")
      (node (ref "E13") (pin "2") (pinfunction "O_2") (pintype "output"))
      (node (ref "E23") (pin "4") (pinfunction "D1_4") (pintype "input"))
    )
    (net (code "106") (name "Net-(E13C-I0)") (class "Default")
      (node (ref "E13") (pin "10") (pinfunction "I1_10") (pintype "input"))
      (node (ref "E13") (pin "9") (pinfunction "I0_9") (pintype "input"))
      (node (ref "U$3") (pin "AD1") (pinfunction "1_AD1") (pintype "bidirectional"))
    )
    (net (code "107") (name "Net-(E13C-O)") (class "Default")
      (node (ref "E13") (pin "14") (pinfunction "O_14") (pintype "output"))
      (node (ref "E23") (pin "12") (pinfunction "D3_12") (pintype "input"))
    )
    (net (code "108") (name "Net-(E13D-I0)") (class "Default")
      (node (ref "E13") (pin "11") (pinfunction "I0_11") (pintype "input"))
      (node (ref "E13") (pin "12") (pinfunction "I1_12") (pintype "input"))
      (node (ref "U$3") (pin "AC1") (pinfunction "1_AC1") (pintype "bidirectional"))
    )
    (net (code "109") (name "Net-(E13D-O)") (class "Default")
      (node (ref "E13") (pin "13") (pinfunction "O_13") (pintype "output"))
      (node (ref "E23") (pin "13") (pinfunction "D4_13") (pintype "input"))
    )
    (net (code "110") (name "Net-(E14A-I0)") (class "Default")
      (node (ref "E14") (pin "4") (pinfunction "I0_4") (pintype "input"))
      (node (ref "E14") (pin "5") (pinfunction "I1_5") (pintype "input"))
      (node (ref "U$3") (pin "BH2") (pinfunction "1_BH2") (pintype "bidirectional"))
    )
    (net (code "111") (name "Net-(E14A-O)") (class "Default")
      (node (ref "E14") (pin "3") (pinfunction "O_3") (pintype "output"))
      (node (ref "E22") (pin "4") (pinfunction "D1_4") (pintype "input"))
    )
    (net (code "112") (name "Net-(E14B-I0)") (class "Default")
      (node (ref "E14") (pin "6") (pinfunction "I0_6") (pintype "input"))
      (node (ref "E14") (pin "7") (pinfunction "I1_7") (pintype "input"))
      (node (ref "U$3") (pin "BF2") (pinfunction "1_BF2") (pintype "bidirectional"))
    )
    (net (code "113") (name "Net-(E14B-O)") (class "Default")
      (node (ref "E14") (pin "2") (pinfunction "O_2") (pintype "output"))
      (node (ref "E22") (pin "5") (pinfunction "D2_5") (pintype "input"))
    )
    (net (code "114") (name "Net-(E14C-I0)") (class "Default")
      (node (ref "E14") (pin "10") (pinfunction "I1_10") (pintype "input"))
      (node (ref "E14") (pin "9") (pinfunction "I0_9") (pintype "input"))
      (node (ref "U$3") (pin "BD2") (pinfunction "1_BD2") (pintype "bidirectional"))
    )
    (net (code "115") (name "Net-(E14C-O)") (class "Default")
      (node (ref "E14") (pin "14") (pinfunction "O_14") (pintype "output"))
      (node (ref "E22") (pin "12") (pinfunction "D3_12") (pintype "input"))
    )
    (net (code "116") (name "Net-(E14D-I0)") (class "Default")
      (node (ref "E14") (pin "11") (pinfunction "I0_11") (pintype "input"))
      (node (ref "E14") (pin "12") (pinfunction "I1_12") (pintype "input"))
      (node (ref "U$3") (pin "BE2") (pinfunction "1_BE2") (pintype "bidirectional"))
    )
    (net (code "117") (name "Net-(E14D-O)") (class "Default")
      (node (ref "E14") (pin "13") (pinfunction "O_13") (pintype "output"))
      (node (ref "E22") (pin "13") (pinfunction "D4_13") (pintype "input"))
    )
    (net (code "118") (name "Net-(E15A-I0)") (class "Default")
      (node (ref "E15") (pin "4") (pinfunction "I0_4") (pintype "input"))
      (node (ref "E15") (pin "5") (pinfunction "I1_5") (pintype "input"))
      (node (ref "U$3") (pin "BF1") (pinfunction "1_BF1") (pintype "bidirectional"))
    )
    (net (code "119") (name "Net-(E15A-O)") (class "Default")
      (node (ref "E15") (pin "3") (pinfunction "O_3") (pintype "output"))
      (node (ref "E19") (pin "12") (pinfunction "D3_12") (pintype "input"))
    )
    (net (code "120") (name "Net-(E15B-I0)") (class "Default")
      (node (ref "E15") (pin "6") (pinfunction "I0_6") (pintype "input"))
      (node (ref "E15") (pin "7") (pinfunction "I1_7") (pintype "input"))
      (node (ref "U$3") (pin "BH1") (pinfunction "1_BH1") (pintype "bidirectional"))
    )
    (net (code "121") (name "Net-(E15B-O)") (class "Default")
      (node (ref "E15") (pin "2") (pinfunction "O_2") (pintype "output"))
      (node (ref "E19") (pin "13") (pinfunction "D4_13") (pintype "input"))
    )
    (net (code "122") (name "Net-(E15C-I0)") (class "Default")
      (node (ref "E15") (pin "10") (pinfunction "I1_10") (pintype "input"))
      (node (ref "E15") (pin "9") (pinfunction "I0_9") (pintype "input"))
      (node (ref "U$3") (pin "BE1") (pinfunction "1_BE1") (pintype "bidirectional"))
    )
    (net (code "123") (name "Net-(E15C-O)") (class "Default")
      (node (ref "E15") (pin "14") (pinfunction "O_14") (pintype "output"))
      (node (ref "E19") (pin "4") (pinfunction "D1_4") (pintype "input"))
    )
    (net (code "124") (name "Net-(E15D-I0)") (class "Default")
      (node (ref "E15") (pin "11") (pinfunction "I0_11") (pintype "input"))
      (node (ref "E15") (pin "12") (pinfunction "I1_12") (pintype "input"))
      (node (ref "U$3") (pin "BD1") (pinfunction "1_BD1") (pintype "bidirectional"))
    )
    (net (code "125") (name "Net-(E15D-O)") (class "Default")
      (node (ref "E15") (pin "13") (pinfunction "O_13") (pintype "output"))
      (node (ref "E19") (pin "5") (pinfunction "D2_5") (pintype "input"))
    )
    (net (code "126") (name "Net-(E16A-I0)") (class "Default")
      (node (ref "E16") (pin "4") (pinfunction "I0_4") (pintype "input"))
      (node (ref "E16") (pin "5") (pinfunction "I1_5") (pintype "input"))
      (node (ref "U$3") (pin "BK1") (pinfunction "1_BK1") (pintype "bidirectional"))
    )
    (net (code "127") (name "Net-(E16A-O)") (class "Default")
      (node (ref "E16") (pin "3") (pinfunction "O_3") (pintype "output"))
      (node (ref "E20") (pin "12") (pinfunction "D3_12") (pintype "input"))
    )
    (net (code "128") (name "Net-(E16B-I0)") (class "Default")
      (node (ref "E16") (pin "6") (pinfunction "I0_6") (pintype "input"))
      (node (ref "E16") (pin "7") (pinfunction "I1_7") (pintype "input"))
      (node (ref "U$3") (pin "BJ1") (pinfunction "1_BJ1") (pintype "bidirectional"))
    )
    (net (code "129") (name "Net-(E16B-O)") (class "Default")
      (node (ref "E16") (pin "2") (pinfunction "O_2") (pintype "output"))
      (node (ref "E20") (pin "13") (pinfunction "D4_13") (pintype "input"))
    )
    (net (code "130") (name "Net-(E16C-I0)") (class "Default")
      (node (ref "E16") (pin "10") (pinfunction "I1_10") (pintype "input"))
      (node (ref "E16") (pin "9") (pinfunction "I0_9") (pintype "input"))
      (node (ref "U$3") (pin "BC1") (pinfunction "1_BC1") (pintype "bidirectional"))
    )
    (net (code "131") (name "Net-(E16C-O)") (class "Default")
      (node (ref "E16") (pin "14") (pinfunction "O_14") (pintype "output"))
      (node (ref "E20") (pin "4") (pinfunction "D1_4") (pintype "input"))
    )
    (net (code "132") (name "Net-(E16D-I0)") (class "Default")
      (node (ref "E16") (pin "11") (pinfunction "I0_11") (pintype "input"))
      (node (ref "E16") (pin "12") (pinfunction "I1_12") (pintype "input"))
      (node (ref "U$3") (pin "BB1") (pinfunction "1_BB1") (pintype "bidirectional"))
    )
    (net (code "133") (name "Net-(E16D-O)") (class "Default")
      (node (ref "E16") (pin "13") (pinfunction "O_13") (pintype "output"))
      (node (ref "E20") (pin "5") (pinfunction "D2_5") (pintype "input"))
    )
    (net (code "134") (name "Net-(E17A-I)") (class "Default")
      (node (ref "E17") (pin "1") (pinfunction "I_1") (pintype "input"))
      (node (ref "U$3") (pin "BJ2") (pinfunction "1_BJ2") (pintype "bidirectional"))
    )
    (net (code "135") (name "Net-(E17A-O)") (class "Default")
      (node (ref "E17") (pin "11") (pinfunction "I_11") (pintype "input"))
      (node (ref "E17") (pin "2") (pinfunction "O_2") (pintype "output"))
    )
    (net (code "136") (name "Net-(E17B-O)") (class "Default")
      (node (ref "E17") (pin "4") (pinfunction "O_4") (pintype "output"))
      (node (ref "U$3") (pin "BN1") (pinfunction "1_BN1") (pintype "bidirectional"))
    )
    (net (code "137") (name "Net-(E17C-O)") (class "Default")
      (node (ref "E17") (pin "6") (pinfunction "O_6") (pintype "output"))
      (node (ref "U$3") (pin "BV2") (pinfunction "1_BV2") (pintype "bidirectional"))
    )
    (net (code "138") (name "Net-(E17D-O)") (class "Default")
      (node (ref "E17") (pin "8") (pinfunction "O_8") (pintype "output"))
      (node (ref "U$3") (pin "BU2") (pinfunction "1_BU2") (pintype "bidirectional"))
    )
    (net (code "139") (name "Net-(E17E-O)") (class "Default")
      (node (ref "E17") (pin "10") (pinfunction "O_10") (pintype "output"))
      (node (ref "E4") (pin "3") (pinfunction "CLK_3") (pintype "input"))
    )
    (net (code "140") (name "Net-(E17F-O)") (class "Default")
      (node (ref "E17") (pin "12") (pinfunction "O_12") (pintype "output"))
      (node (ref "U$3") (pin "BP1") (pinfunction "1_BP1") (pintype "bidirectional"))
    )
    (net (code "141") (name "Net-(E18A-O)") (class "Default")
      (node (ref "E18") (pin "2") (pinfunction "O_2") (pintype "output"))
      (node (ref "U$3") (pin "BL2") (pinfunction "1_BL2") (pintype "bidirectional"))
    )
    (net (code "142") (name "Net-(E18B-O)") (class "Default")
      (node (ref "E18") (pin "4") (pinfunction "O_4") (pintype "output"))
      (node (ref "U$3") (pin "BM2") (pinfunction "1_BM2") (pintype "bidirectional"))
    )
    (net (code "143") (name "Net-(E18C-O)") (class "Default")
      (node (ref "E18") (pin "6") (pinfunction "O_6") (pintype "output"))
      (node (ref "U$3") (pin "BN2") (pinfunction "1_BN2") (pintype "bidirectional"))
    )
    (net (code "144") (name "Net-(E18D-O)") (class "Default")
      (node (ref "E18") (pin "8") (pinfunction "O_8") (pintype "output"))
      (node (ref "U$3") (pin "BK2") (pinfunction "1_BK2") (pintype "bidirectional"))
    )
    (net (code "145") (name "Net-(E18E-O)") (class "Default")
      (node (ref "E18") (pin "10") (pinfunction "O_10") (pintype "output"))
      (node (ref "U$3") (pin "BL1") (pinfunction "1_BL1") (pintype "bidirectional"))
    )
    (net (code "146") (name "Net-(E18F-O)") (class "Default")
      (node (ref "E18") (pin "12") (pinfunction "O_12") (pintype "output"))
      (node (ref "U$3") (pin "BM1") (pinfunction "1_BM1") (pintype "bidirectional"))
    )
    (net (code "147") (name "Net-(E21A-O)") (class "Default")
      (node (ref "E21") (pin "2") (pinfunction "O_2") (pintype "output"))
      (node (ref "U$3") (pin "BR2") (pinfunction "1_BR2") (pintype "bidirectional"))
    )
    (net (code "148") (name "Net-(E21B-O)") (class "Default")
      (node (ref "E21") (pin "4") (pinfunction "O_4") (pintype "output"))
      (node (ref "U$3") (pin "BS2") (pinfunction "1_BS2") (pintype "bidirectional"))
    )
    (net (code "149") (name "Net-(E21C-O)") (class "Default")
      (node (ref "E21") (pin "6") (pinfunction "O_6") (pintype "output"))
      (node (ref "U$3") (pin "BU1") (pinfunction "1_BU1") (pintype "bidirectional"))
    )
    (net (code "150") (name "Net-(E21D-O)") (class "Default")
      (node (ref "E21") (pin "8") (pinfunction "O_8") (pintype "output"))
      (node (ref "U$3") (pin "BP2") (pinfunction "1_BP2") (pintype "bidirectional"))
    )
    (net (code "151") (name "Net-(E21E-O)") (class "Default")
      (node (ref "E21") (pin "10") (pinfunction "O_10") (pintype "output"))
      (node (ref "U$3") (pin "BR1") (pinfunction "1_BR1") (pintype "bidirectional"))
    )
    (net (code "152") (name "Net-(E21F-O)") (class "Default")
      (node (ref "E21") (pin "12") (pinfunction "O_12") (pintype "output"))
      (node (ref "U$3") (pin "BS1") (pinfunction "1_BS1") (pintype "bidirectional"))
    )
    (net (code "153") (name "Net-(E22A-Q1)") (class "Default")
      (node (ref "E22") (pin "2") (pinfunction "Q1_2") (pintype "output"))
      (node (ref "E9") (pin "11") (pinfunction "I_11") (pintype "input"))
    )
    (net (code "154") (name "Net-(E22A-Q2)") (class "Default")
      (node (ref "E22") (pin "7") (pinfunction "Q2_7") (pintype "output"))
      (node (ref "E9") (pin "9") (pinfunction "I_9") (pintype "input"))
    )
    (net (code "155") (name "Net-(E23A-Q1)") (class "Default")
      (node (ref "E23") (pin "2") (pinfunction "Q1_2") (pintype "output"))
      (node (ref "E9") (pin "3") (pinfunction "I_3") (pintype "input"))
    )
    (net (code "156") (name "Net-(E23A-Q2)") (class "Default")
      (node (ref "E23") (pin "7") (pinfunction "Q2_7") (pintype "output"))
      (node (ref "E9") (pin "5") (pinfunction "I_5") (pintype "input"))
    )
    (net (code "157") (name "Net-(J1M-P$2)") (class "Default")
      (node (ref "D3") (pin "C") (pinfunction "C_C") (pintype "passive"))
      (node (ref "D4") (pin "A") (pinfunction "A_A") (pintype "passive"))
      (node (ref "J1") (pin "X") (pinfunction "P$2_X") (pintype "passive"))
      (node (ref "U$3") (pin "AL1") (pinfunction "1_AL1") (pintype "bidirectional"))
    )
    (net (code "158") (name "Net-(J1O-P$2)") (class "Default")
      (node (ref "D1") (pin "C") (pinfunction "C_C") (pintype "passive"))
      (node (ref "D2") (pin "A") (pinfunction "A_A") (pintype "passive"))
      (node (ref "J1") (pin "Z") (pinfunction "P$2_Z") (pintype "passive"))
      (node (ref "U$3") (pin "AR2") (pinfunction "1_AR2") (pintype "bidirectional"))
    )
    (net (code "159") (name "VCC") (class "Default")
      (node (ref "C1") (pin "1") (pinfunction "1_1") (pintype "passive"))
      (node (ref "C10") (pin "1") (pinfunction "1_1") (pintype "passive"))
      (node (ref "C11") (pin "1") (pinfunction "1_1") (pintype "passive"))
      (node (ref "C12") (pin "1") (pinfunction "1_1") (pintype "passive"))
      (node (ref "C13") (pin "1") (pinfunction "1_1") (pintype "passive"))
      (node (ref "C14") (pin "1") (pinfunction "1_1") (pintype "passive"))
      (node (ref "C15") (pin "1") (pinfunction "1_1") (pintype "passive"))
      (node (ref "C16") (pin "1") (pinfunction "1_1") (pintype "passive"))
      (node (ref "C17") (pin "1") (pinfunction "1_1") (pintype "passive"))
      (node (ref "C18") (pin "1") (pinfunction "1_1") (pintype "passive"))
      (node (ref "C19") (pin "1") (pinfunction "1_1") (pintype "passive"))
      (node (ref "C2") (pin "1") (pinfunction "1_1") (pintype "passive"))
      (node (ref "C20") (pin "1") (pinfunction "1_1") (pintype "passive"))
      (node (ref "C21") (pin "1") (pinfunction "1_1") (pintype "passive"))
      (node (ref "C22") (pin "1") (pinfunction "1_1") (pintype "passive"))
      (node (ref "C23") (pin "1") (pinfunction "1_1") (pintype "passive"))
      (node (ref "C24") (pin "+") (pinfunction "+_+") (pintype "passive"))
      (node (ref "C3") (pin "1") (pinfunction "1_1") (pintype "passive"))
      (node (ref "C4") (pin "1") (pinfunction "1_1") (pintype "passive"))
      (node (ref "C5") (pin "1") (pinfunction "1_1") (pintype "passive"))
      (node (ref "C6") (pin "1") (pinfunction "1_1") (pintype "passive"))
      (node (ref "C7") (pin "1") (pinfunction "1_1") (pintype "passive"))
      (node (ref "C8") (pin "1") (pinfunction "1_1") (pintype "passive"))
      (node (ref "C9") (pin "1") (pinfunction "1_1") (pintype "passive"))
      (node (ref "D2") (pin "C") (pinfunction "C_C") (pintype "passive"))
      (node (ref "D4") (pin "C") (pinfunction "C_C") (pintype "passive"))
      (node (ref "R10") (pin "2") (pinfunction "2_2") (pintype "passive"))
      (node (ref "R11") (pin "2") (pinfunction "2_2") (pintype "passive"))
      (node (ref "R12") (pin "2") (pinfunction "2_2") (pintype "passive"))
      (node (ref "R13") (pin "2") (pinfunction "2_2") (pintype "passive"))
      (node (ref "R14") (pin "2") (pinfunction "2_2") (pintype "passive"))
      (node (ref "R15") (pin "2") (pinfunction "2_2") (pintype "passive"))
      (node (ref "R16") (pin "2") (pinfunction "2_2") (pintype "passive"))
      (node (ref "R17") (pin "2") (pinfunction "2_2") (pintype "passive"))
      (node (ref "R18") (pin "2") (pinfunction "2_2") (pintype "passive"))
      (node (ref "R19") (pin "2") (pinfunction "2_2") (pintype "passive"))
      (node (ref "R2") (pin "2") (pinfunction "2_2") (pintype "passive"))
      (node (ref "R20") (pin "2") (pinfunction "2_2") (pintype "passive"))
      (node (ref "R3") (pin "2") (pinfunction "2_2") (pintype "passive"))
      (node (ref "R4") (pin "2") (pinfunction "2_2") (pintype "passive"))
      (node (ref "R5") (pin "2") (pinfunction "2_2") (pintype "passive"))
      (node (ref "R6") (pin "2") (pinfunction "2_2") (pintype "passive"))
      (node (ref "R7") (pin "2") (pinfunction "2_2") (pintype "passive"))
      (node (ref "R8") (pin "2") (pinfunction "2_2") (pintype "passive"))
      (node (ref "R9") (pin "2") (pinfunction "2_2") (pintype "passive"))
      (node (ref "U$3") (pin "AA2") (pinfunction "1_AA2") (pintype "bidirectional"))
      (node (ref "U$3") (pin "BA2") (pinfunction "1_BA2") (pintype "bidirectional"))
    )
    (net (code "160") (name "unconnected-(E4A-Q-Pad5)") (class "Default")
      (node (ref "E4") (pin "5") (pinfunction "Q_5") (pintype "output"))
    )
  )
)
